# hover_controller_v2.net
KiCad netlist of a schematic drawn in EAGLE
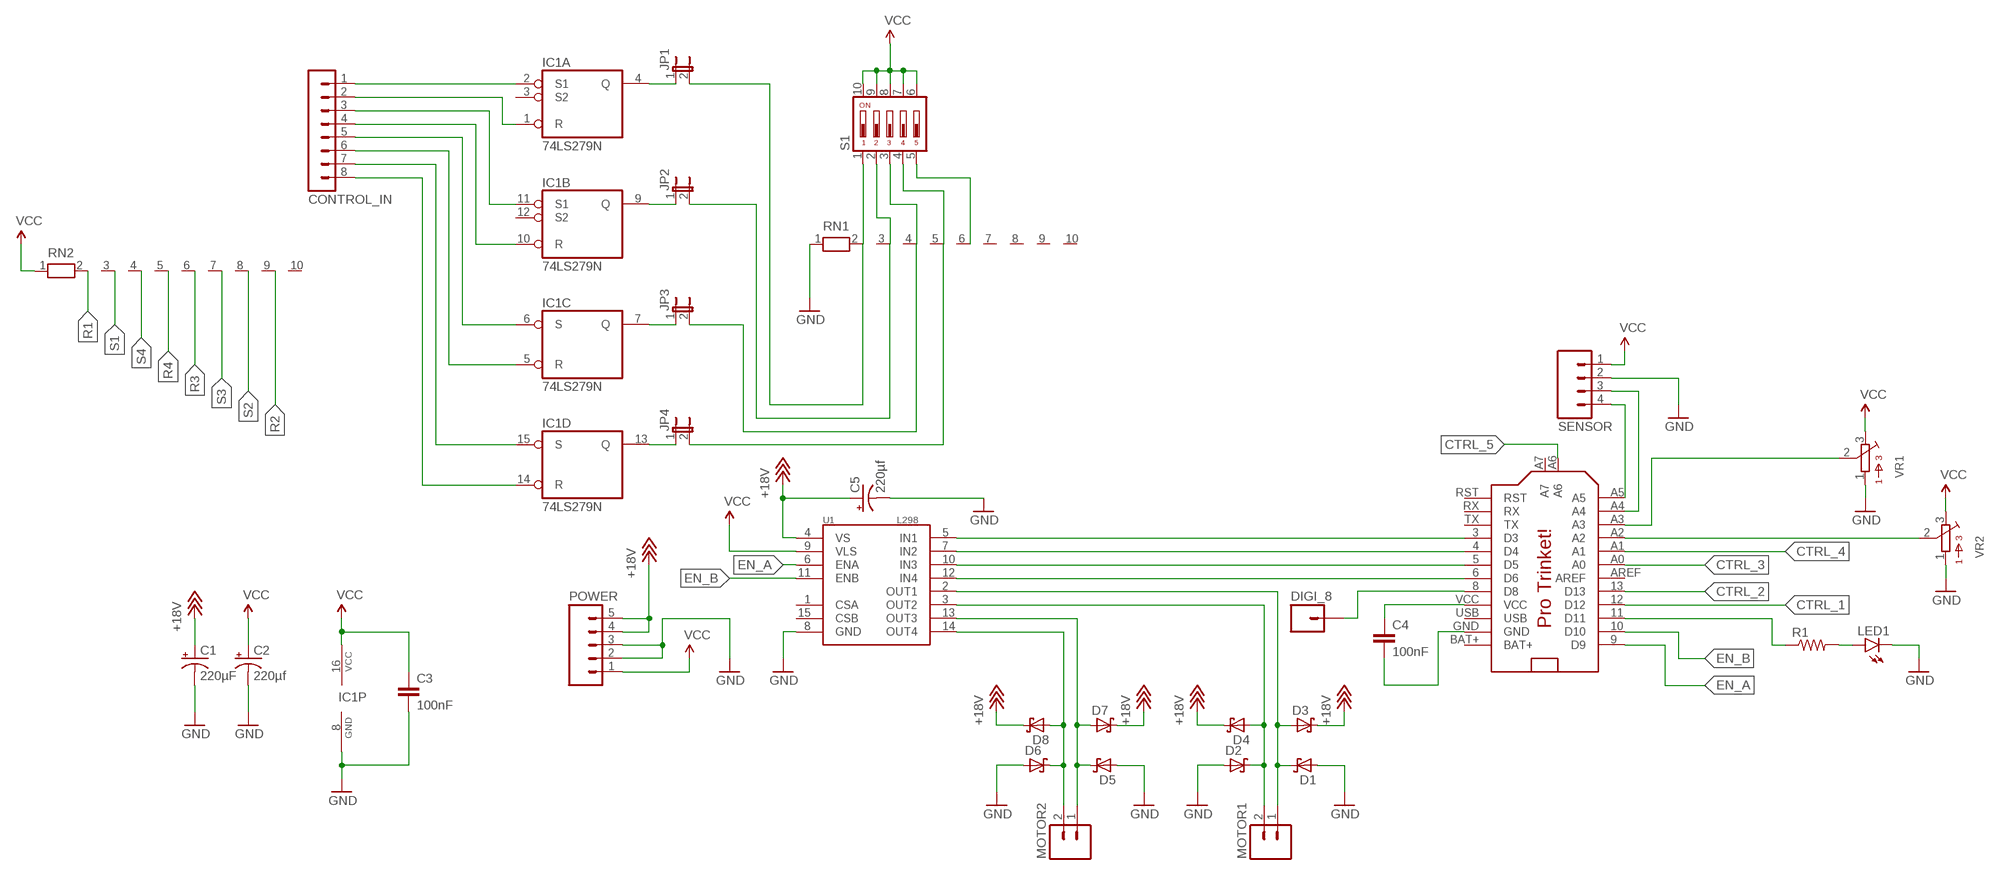
[diagram p0: schematic, sheet 1]

(export (version "E")
  (design (tool "Eeschema 10.0.6"))
  (components
    (comp (ref "C1")
      (value "220µF")
      (footprint "eagle-import:CPOL-RADIAL-10UF-25V")
      (libsource (lib "eagle-import") (part "CAP_POLPTH2"))
    )
    (comp (ref "C2")
      (value "220µf")
      (footprint "eagle-import:CPOL-RADIAL-10UF-25V")
      (libsource (lib "eagle-import") (part "CAP_POLPTH2"))
    )
    (comp (ref "C3")
      (value "100nF")
      (footprint "eagle-import:CAP-PTH-5MM")
      (libsource (lib "eagle-import") (part "CAPPTH1"))
    )
    (comp (ref "C4")
      (value "100nF")
      (footprint "eagle-import:CAP-PTH-5MM")
      (libsource (lib "eagle-import") (part "CAPPTH1"))
    )
    (comp (ref "C5")
      (value "220µf")
      (footprint "eagle-import:CPOL-RADIAL-10UF-25V")
      (libsource (lib "eagle-import") (part "CAP_POLPTH2"))
    )
    (comp (ref "CONTROL_IN")
      (value "MA08-1")
      (footprint "eagle-import:MA08-1")
      (libsource (lib "eagle-import") (part "MA08-1"))
    )
    (comp (ref "D1")
      (value "SCHOTTKY-DIODEDO35-7")
      (footprint "eagle-import:DO35-7")
      (libsource (lib "eagle-import") (part "SCHOTTKY-DIODEDO35-7"))
    )
    (comp (ref "D2")
      (value "SCHOTTKY-DIODEDO35-7")
      (footprint "eagle-import:DO35-7")
      (libsource (lib "eagle-import") (part "SCHOTTKY-DIODEDO35-7"))
    )
    (comp (ref "D3")
      (value "SCHOTTKY-DIODEDO35-7")
      (footprint "eagle-import:DO35-7")
      (libsource (lib "eagle-import") (part "SCHOTTKY-DIODEDO35-7"))
    )
    (comp (ref "D4")
      (value "SCHOTTKY-DIODEDO35-7")
      (footprint "eagle-import:DO35-7")
      (libsource (lib "eagle-import") (part "SCHOTTKY-DIODEDO35-7"))
    )
    (comp (ref "D5")
      (value "SCHOTTKY-DIODEDO35-7")
      (footprint "eagle-import:DO35-7")
      (libsource (lib "eagle-import") (part "SCHOTTKY-DIODEDO35-7"))
    )
    (comp (ref "D6")
      (value "SCHOTTKY-DIODEDO35-7")
      (footprint "eagle-import:DO35-7")
      (libsource (lib "eagle-import") (part "SCHOTTKY-DIODEDO35-7"))
    )
    (comp (ref "D7")
      (value "SCHOTTKY-DIODEDO35-7")
      (footprint "eagle-import:DO35-7")
      (libsource (lib "eagle-import") (part "SCHOTTKY-DIODEDO35-7"))
    )
    (comp (ref "D8")
      (value "SCHOTTKY-DIODEDO35-7")
      (footprint "eagle-import:DO35-7")
      (libsource (lib "eagle-import") (part "SCHOTTKY-DIODEDO35-7"))
    )
    (comp (ref "DIGI_8")
      (value "M01PTH")
      (footprint "eagle-import:1X01")
      (libsource (lib "eagle-import") (part "M01PTH"))
    )
    (comp (ref "IC1")
      (value "74LS279N")
      (footprint "eagle-import:DIL16")
      (libsource (lib "eagle-import") (part "74279NLS"))
    )
    (comp (ref "JP1")
      (value "JUMPER-2PTH")
      (footprint "eagle-import:1X02")
      (libsource (lib "eagle-import") (part "JUMPER-2PTH"))
    )
    (comp (ref "JP2")
      (value "JUMPER-2PTH")
      (footprint "eagle-import:1X02")
      (libsource (lib "eagle-import") (part "JUMPER-2PTH"))
    )
    (comp (ref "JP3")
      (value "JUMPER-2PTH")
      (footprint "eagle-import:1X02")
      (libsource (lib "eagle-import") (part "JUMPER-2PTH"))
    )
    (comp (ref "JP4")
      (value "JUMPER-2PTH")
      (footprint "eagle-import:1X02")
      (libsource (lib "eagle-import") (part "JUMPER-2PTH"))
    )
    (comp (ref "LED1")
      (value "LED-3MM-NO_SILK")
      (footprint "eagle-import:LED3MM-NS")
      (libsource (lib "eagle-import") (part "LED-3MM-NO_SILK"))
    )
    (comp (ref "MOTOR1")
      (value "M02PTH")
      (footprint "eagle-import:1X02")
      (libsource (lib "eagle-import") (part "M02PTH"))
    )
    (comp (ref "MOTOR2")
      (value "M02PTH")
      (footprint "eagle-import:1X02")
      (libsource (lib "eagle-import") (part "M02PTH"))
    )
    (comp (ref "POWER")
      (value "M05JST-VERT")
      (footprint "eagle-import:JST-5-PTH-VERT")
      (libsource (lib "eagle-import") (part "M05JST-VERT"))
    )
    (comp (ref "R1")
      (value "RESISTORPTH-1/4W")
      (footprint "eagle-import:AXIAL-0.4")
      (libsource (lib "eagle-import") (part "RESISTORPTH-1/4W"))
    )
    (comp (ref "RN1")
      (value "RN09")
      (footprint "eagle-import:RN-10")
      (libsource (lib "eagle-import") (part "RN09"))
    )
    (comp (ref "RN2")
      (value "RN09")
      (footprint "eagle-import:RN-10")
      (libsource (lib "eagle-import") (part "RN09"))
    )
    (comp (ref "S1")
      (value "DIP05YL")
      (footprint "eagle-import:DIP05YL")
      (libsource (lib "eagle-import") (part "DIP05YL"))
    )
    (comp (ref "SENSOR")
      (value "M04PTH")
      (footprint "eagle-import:1X04")
      (libsource (lib "eagle-import") (part "M04PTH"))
    )
    (comp (ref "U$1")
      (value "PRO_TRINKET")
      (footprint "eagle-import:PROTRINKET")
      (libsource (lib "eagle-import") (part "PRO_TRINKET"))
    )
    (comp (ref "U1")
      (value "L298")
      (footprint "eagle-import:MULTIWATT15")
      (libsource (lib "eagle-import") (part "L298"))
    )
    (comp (ref "VR1")
      (value "BOURNS_3362P_TRIMMERP")
      (footprint "eagle-import:BOURNS_3362P_TRIMMER")
      (libsource (lib "eagle-import") (part "BOURNS_3362P_TRIMMERP"))
    )
    (comp (ref "VR2")
      (value "BOURNS_3362P_TRIMMERP")
      (footprint "eagle-import:BOURNS_3362P_TRIMMER")
      (libsource (lib "eagle-import") (part "BOURNS_3362P_TRIMMERP"))
    )
  )
  (nets
    (net (code "1") (name "+18V") (class "Default")
      (node (ref "C1") (pin "1") (pinfunction "+_1") (pintype "passive"))
      (node (ref "C5") (pin "1") (pinfunction "+_1") (pintype "passive"))
      (node (ref "D3") (pin "C") (pinfunction "C_C") (pintype "passive"))
      (node (ref "D4") (pin "C") (pinfunction "C_C") (pintype "passive"))
      (node (ref "D7") (pin "C") (pinfunction "C_C") (pintype "passive"))
      (node (ref "D8") (pin "C") (pinfunction "C_C") (pintype "passive"))
      (node (ref "POWER") (pin "4") (pinfunction "4_4") (pintype "passive"))
      (node (ref "POWER") (pin "5") (pinfunction "5_5") (pintype "passive"))
      (node (ref "U1") (pin "4") (pinfunction "VS_4") (pintype "bidirectional"))
    )
    (net (code "2") (name "/BAT+") (class "Default")
      (node (ref "U$1") (pin "BAT+") (pinfunction "BAT+_BAT+") (pintype "power_in"))
    )
    (net (code "3") (name "/USB") (class "Default")
      (node (ref "U$1") (pin "USB") (pinfunction "USB_USB") (pintype "power_in"))
    )
    (net (code "4") (name "CTRL_1") (class "Default")
      (node (ref "JP1") (pin "2") (pinfunction "2_2") (pintype "passive"))
      (node (ref "RN1") (pin "2") (pinfunction "2_2") (pintype "passive"))
      (node (ref "S1") (pin "1") (pinfunction "1_1") (pintype "passive"))
      (node (ref "U$1") (pin "12") (pinfunction "D12_12") (pintype "bidirectional"))
    )
    (net (code "5") (name "CTRL_2") (class "Default")
      (node (ref "JP2") (pin "2") (pinfunction "2_2") (pintype "passive"))
      (node (ref "RN1") (pin "3") (pinfunction "3_3") (pintype "passive"))
      (node (ref "S1") (pin "2") (pinfunction "2_2") (pintype "passive"))
      (node (ref "U$1") (pin "13") (pinfunction "D13_13") (pintype "bidirectional"))
    )
    (net (code "6") (name "CTRL_3") (class "Default")
      (node (ref "JP3") (pin "2") (pinfunction "2_2") (pintype "passive"))
      (node (ref "RN1") (pin "4") (pinfunction "4_4") (pintype "passive"))
      (node (ref "S1") (pin "3") (pinfunction "3_3") (pintype "passive"))
      (node (ref "U$1") (pin "A0") (pinfunction "A0_A0") (pintype "bidirectional"))
    )
    (net (code "7") (name "CTRL_4") (class "Default")
      (node (ref "JP4") (pin "2") (pinfunction "2_2") (pintype "passive"))
      (node (ref "RN1") (pin "5") (pinfunction "5_5") (pintype "passive"))
      (node (ref "S1") (pin "4") (pinfunction "4_4") (pintype "passive"))
      (node (ref "U$1") (pin "A1") (pinfunction "A1_A1") (pintype "bidirectional"))
    )
    (net (code "8") (name "CTRL_5") (class "Default")
      (node (ref "RN1") (pin "6") (pinfunction "6_6") (pintype "passive"))
      (node (ref "S1") (pin "5") (pinfunction "5_5") (pintype "passive"))
      (node (ref "U$1") (pin "A6") (pinfunction "A6_A6") (pintype "passive"))
    )
    (net (code "9") (name "EN_A") (class "Default")
      (node (ref "U$1") (pin "9") (pinfunction "D9_9") (pintype "bidirectional"))
      (node (ref "U1") (pin "6") (pinfunction "ENA_6") (pintype "bidirectional"))
    )
    (net (code "10") (name "EN_B") (class "Default")
      (node (ref "U$1") (pin "10") (pinfunction "D10_10") (pintype "bidirectional"))
      (node (ref "U1") (pin "11") (pinfunction "ENB_11") (pintype "bidirectional"))
    )
    (net (code "11") (name "GND") (class "Default")
      (node (ref "C1") (pin "2") (pinfunction "-_2") (pintype "passive"))
      (node (ref "C2") (pin "2") (pinfunction "-_2") (pintype "passive"))
      (node (ref "C3") (pin "2") (pinfunction "2_2") (pintype "passive"))
      (node (ref "C5") (pin "2") (pinfunction "-_2") (pintype "passive"))
      (node (ref "D1") (pin "A") (pinfunction "A_A") (pintype "passive"))
      (node (ref "D2") (pin "A") (pinfunction "A_A") (pintype "passive"))
      (node (ref "D5") (pin "A") (pinfunction "A_A") (pintype "passive"))
      (node (ref "D6") (pin "A") (pinfunction "A_A") (pintype "passive"))
      (node (ref "IC1") (pin "8") (pinfunction "GND_8") (pintype "power_in"))
      (node (ref "LED1") (pin "K") (pinfunction "C_K") (pintype "passive"))
      (node (ref "POWER") (pin "2") (pinfunction "2_2") (pintype "passive"))
      (node (ref "POWER") (pin "3") (pinfunction "3_3") (pintype "passive"))
      (node (ref "RN1") (pin "1") (pinfunction "1_1") (pintype "passive"))
      (node (ref "SENSOR") (pin "2") (pinfunction "2_2") (pintype "passive"))
      (node (ref "U1") (pin "8") (pinfunction "GND_8") (pintype "bidirectional"))
      (node (ref "VR1") (pin "1") (pinfunction "1_1") (pintype "passive"))
      (node (ref "VR2") (pin "1") (pinfunction "1_1") (pintype "passive"))
    )
    (net (code "12") (name "Net-(C4-Pad1)") (class "Default")
      (node (ref "C4") (pin "1") (pinfunction "1_1") (pintype "passive"))
      (node (ref "U$1") (pin "VCC") (pinfunction "VCC_VCC") (pintype "power_in"))
    )
    (net (code "13") (name "Net-(C4-Pad2)") (class "Default")
      (node (ref "C4") (pin "2") (pinfunction "2_2") (pintype "passive"))
      (node (ref "U$1") (pin "GND") (pinfunction "GND_GND") (pintype "power_in"))
    )
    (net (code "14") (name "Net-(IC1A-Q)") (class "Default")
      (node (ref "IC1") (pin "4") (pinfunction "Q_4") (pintype "output"))
      (node (ref "JP1") (pin "1") (pinfunction "1_1") (pintype "passive"))
    )
    (net (code "15") (name "Net-(IC1B-Q)") (class "Default")
      (node (ref "IC1") (pin "9") (pinfunction "Q_9") (pintype "output"))
      (node (ref "JP2") (pin "1") (pinfunction "1_1") (pintype "passive"))
    )
    (net (code "16") (name "Net-(IC1C-Q)") (class "Default")
      (node (ref "IC1") (pin "7") (pinfunction "Q_7") (pintype "output"))
      (node (ref "JP3") (pin "1") (pinfunction "1_1") (pintype "passive"))
    )
    (net (code "17") (name "Net-(IC1D-Q)") (class "Default")
      (node (ref "IC1") (pin "13") (pinfunction "Q_13") (pintype "output"))
      (node (ref "JP4") (pin "1") (pinfunction "1_1") (pintype "passive"))
    )
    (net (code "18") (name "Net-(R1-1)") (class "Default")
      (node (ref "R1") (pin "P$1") (pinfunction "1_P$1") (pintype "passive"))
      (node (ref "U$1") (pin "11") (pinfunction "D11_11") (pintype "bidirectional"))
    )
    (net (code "19") (name "Net-(R1-2)") (class "Default")
      (node (ref "LED1") (pin "A") (pinfunction "A_A") (pintype "passive"))
      (node (ref "R1") (pin "P$2") (pinfunction "2_P$2") (pintype "passive"))
    )
    (net (code "20") (name "Net-(SENSOR-Pad3)") (class "Default")
      (node (ref "SENSOR") (pin "3") (pinfunction "3_3") (pintype "passive"))
      (node (ref "U$1") (pin "A4") (pinfunction "A4_A4") (pintype "bidirectional"))
    )
    (net (code "21") (name "Net-(SENSOR-Pad4)") (class "Default")
      (node (ref "SENSOR") (pin "4") (pinfunction "4_4") (pintype "passive"))
      (node (ref "U$1") (pin "A5") (pinfunction "A5_A5") (pintype "bidirectional"))
    )
    (net (code "22") (name "Net-(U$1-D3)") (class "Default")
      (node (ref "U$1") (pin "3") (pinfunction "D3_3") (pintype "bidirectional"))
      (node (ref "U1") (pin "5") (pinfunction "IN1_5") (pintype "bidirectional"))
    )
    (net (code "23") (name "Net-(U$1-D4)") (class "Default")
      (node (ref "U$1") (pin "4") (pinfunction "D4_4") (pintype "bidirectional"))
      (node (ref "U1") (pin "7") (pinfunction "IN2_7") (pintype "bidirectional"))
    )
    (net (code "24") (name "Net-(U$1-D5)") (class "Default")
      (node (ref "U$1") (pin "5") (pinfunction "D5_5") (pintype "bidirectional"))
      (node (ref "U1") (pin "10") (pinfunction "IN3_10") (pintype "bidirectional"))
    )
    (net (code "25") (name "Net-(U$1-D6)") (class "Default")
      (node (ref "U$1") (pin "6") (pinfunction "D6_6") (pintype "bidirectional"))
      (node (ref "U1") (pin "12") (pinfunction "IN4_12") (pintype "bidirectional"))
    )
    (net (code "26") (name "Net-(U$1-D8)") (class "Default")
      (node (ref "DIGI_8") (pin "1") (pinfunction "1_1") (pintype "passive"))
      (node (ref "U$1") (pin "8") (pinfunction "D8_8") (pintype "bidirectional"))
    )
    (net (code "27") (name "Net-(U$1-PadA2)") (class "Default")
      (node (ref "U$1") (pin "A2") (pinfunction "A2_A2") (pintype "bidirectional"))
      (node (ref "VR2") (pin "2") (pinfunction "2_2") (pintype "passive"))
    )
    (net (code "28") (name "Net-(U$1-PadA3)") (class "Default")
      (node (ref "U$1") (pin "A3") (pinfunction "A3_A3") (pintype "bidirectional"))
      (node (ref "VR1") (pin "2") (pinfunction "2_2") (pintype "passive"))
    )
    (net (code "29") (name "Net-(U1-OUT1)") (class "Default")
      (node (ref "D1") (pin "C") (pinfunction "C_C") (pintype "passive"))
      (node (ref "D3") (pin "A") (pinfunction "A_A") (pintype "passive"))
      (node (ref "MOTOR1") (pin "1") (pinfunction "1_1") (pintype "passive"))
      (node (ref "U1") (pin "2") (pinfunction "OUT1_2") (pintype "bidirectional"))
    )
    (net (code "30") (name "Net-(U1-OUT2)") (class "Default")
      (node (ref "D2") (pin "C") (pinfunction "C_C") (pintype "passive"))
      (node (ref "D4") (pin "A") (pinfunction "A_A") (pintype "passive"))
      (node (ref "MOTOR1") (pin "2") (pinfunction "2_2") (pintype "passive"))
      (node (ref "U1") (pin "3") (pinfunction "OUT2_3") (pintype "bidirectional"))
    )
    (net (code "31") (name "Net-(U1-OUT3)") (class "Default")
      (node (ref "D5") (pin "C") (pinfunction "C_C") (pintype "passive"))
      (node (ref "D7") (pin "A") (pinfunction "A_A") (pintype "passive"))
      (node (ref "MOTOR2") (pin "1") (pinfunction "1_1") (pintype "passive"))
      (node (ref "U1") (pin "13") (pinfunction "OUT3_13") (pintype "bidirectional"))
    )
    (net (code "32") (name "Net-(U1-OUT4)") (class "Default")
      (node (ref "D6") (pin "C") (pinfunction "C_C") (pintype "passive"))
      (node (ref "D8") (pin "A") (pinfunction "A_A") (pintype "passive"))
      (node (ref "MOTOR2") (pin "2") (pinfunction "2_2") (pintype "passive"))
      (node (ref "U1") (pin "14") (pinfunction "OUT4_14") (pintype "bidirectional"))
    )
    (net (code "33") (name "R1") (class "Default")
      (node (ref "CONTROL_IN") (pin "2") (pinfunction "2_2") (pintype "passive"))
      (node (ref "IC1") (pin "1") (pinfunction "R_1") (pintype "input"))
      (node (ref "RN2") (pin "2") (pinfunction "2_2") (pintype "passive"))
    )
    (net (code "34") (name "R2") (class "Default")
      (node (ref "CONTROL_IN") (pin "4") (pinfunction "4_4") (pintype "passive"))
      (node (ref "IC1") (pin "10") (pinfunction "R_10") (pintype "input"))
      (node (ref "RN2") (pin "9") (pinfunction "9_9") (pintype "passive"))
    )
    (net (code "35") (name "R3") (class "Default")
      (node (ref "CONTROL_IN") (pin "6") (pinfunction "6_6") (pintype "passive"))
      (node (ref "IC1") (pin "5") (pinfunction "R_5") (pintype "input"))
      (node (ref "RN2") (pin "6") (pinfunction "6_6") (pintype "passive"))
    )
    (net (code "36") (name "R4") (class "Default")
      (node (ref "CONTROL_IN") (pin "8") (pinfunction "8_8") (pintype "passive"))
      (node (ref "IC1") (pin "14") (pinfunction "R_14") (pintype "input"))
      (node (ref "RN2") (pin "5") (pinfunction "5_5") (pintype "passive"))
    )
    (net (code "37") (name "S1") (class "Default")
      (node (ref "CONTROL_IN") (pin "1") (pinfunction "1_1") (pintype "passive"))
      (node (ref "IC1") (pin "2") (pinfunction "S1_2") (pintype "input"))
      (node (ref "RN2") (pin "3") (pinfunction "3_3") (pintype "passive"))
    )
    (net (code "38") (name "S2") (class "Default")
      (node (ref "CONTROL_IN") (pin "3") (pinfunction "3_3") (pintype "passive"))
      (node (ref "IC1") (pin "11") (pinfunction "S1_11") (pintype "input"))
      (node (ref "RN2") (pin "8") (pinfunction "8_8") (pintype "passive"))
    )
    (net (code "39") (name "S3") (class "Default")
      (node (ref "CONTROL_IN") (pin "5") (pinfunction "5_5") (pintype "passive"))
      (node (ref "IC1") (pin "6") (pinfunction "S_6") (pintype "input"))
      (node (ref "RN2") (pin "7") (pinfunction "7_7") (pintype "passive"))
    )
    (net (code "40") (name "S4") (class "Default")
      (node (ref "CONTROL_IN") (pin "7") (pinfunction "7_7") (pintype "passive"))
      (node (ref "IC1") (pin "15") (pinfunction "S_15") (pintype "input"))
      (node (ref "RN2") (pin "4") (pinfunction "4_4") (pintype "passive"))
    )
    (net (code "41") (name "VCC") (class "Default")
      (node (ref "C2") (pin "1") (pinfunction "+_1") (pintype "passive"))
      (node (ref "C3") (pin "1") (pinfunction "1_1") (pintype "passive"))
      (node (ref "IC1") (pin "16") (pinfunction "VCC_16") (pintype "power_in"))
      (node (ref "POWER") (pin "1") (pinfunction "1_1") (pintype "passive"))
      (node (ref "RN2") (pin "1") (pinfunction "1_1") (pintype "passive"))
      (node (ref "S1") (pin "10") (pinfunction "10_10") (pintype "passive"))
      (node (ref "S1") (pin "6") (pinfunction "6_6") (pintype "passive"))
      (node (ref "S1") (pin "7") (pinfunction "7_7") (pintype "passive"))
      (node (ref "S1") (pin "8") (pinfunction "8_8") (pintype "passive"))
      (node (ref "S1") (pin "9") (pinfunction "9_9") (pintype "passive"))
      (node (ref "SENSOR") (pin "1") (pinfunction "1_1") (pintype "passive"))
      (node (ref "U1") (pin "9") (pinfunction "VLS_9") (pintype "bidirectional"))
      (node (ref "VR1") (pin "3") (pinfunction "3_3") (pintype "passive"))
      (node (ref "VR2") (pin "3") (pinfunction "3_3") (pintype "passive"))
    )
    (net (code "42") (name "unconnected-(IC1A-S2-Pad3)") (class "Default")
      (node (ref "IC1") (pin "3") (pinfunction "S2_3") (pintype "input"))
    )
    (net (code "43") (name "unconnected-(IC1B-S2-Pad12)") (class "Default")
      (node (ref "IC1") (pin "12") (pinfunction "S2_12") (pintype "input"))
    )
    (net (code "44") (name "unconnected-(RN1-Pad7)") (class "Default")
      (node (ref "RN1") (pin "7") (pinfunction "7_7") (pintype "passive"))
    )
    (net (code "45") (name "unconnected-(RN1-Pad8)") (class "Default")
      (node (ref "RN1") (pin "8") (pinfunction "8_8") (pintype "passive"))
    )
    (net (code "46") (name "unconnected-(RN1-Pad9)") (class "Default")
      (node (ref "RN1") (pin "9") (pinfunction "9_9") (pintype "passive"))
    )
    (net (code "47") (name "unconnected-(RN1-Pad10)") (class "Default")
      (node (ref "RN1") (pin "10") (pinfunction "10_10") (pintype "passive"))
    )
    (net (code "48") (name "unconnected-(RN2-Pad10)") (class "Default")
      (node (ref "RN2") (pin "10") (pinfunction "10_10") (pintype "passive"))
    )
    (net (code "49") (name "unconnected-(U$1-PadA7)") (class "Default")
      (node (ref "U$1") (pin "A7") (pinfunction "A7_A7") (pintype "passive"))
    )
    (net (code "50") (name "unconnected-(U$1-PadAREF)") (class "Default")
      (node (ref "U$1") (pin "AREF") (pinfunction "AREF_AREF") (pintype "passive"))
    )
    (net (code "51") (name "unconnected-(U$1-PadRST)") (class "Default")
      (node (ref "U$1") (pin "RST") (pinfunction "RST_RST") (pintype "passive"))
    )
    (net (code "52") (name "unconnected-(U$1-PadRX)") (class "Default")
      (node (ref "U$1") (pin "RX") (pinfunction "RX_RX") (pintype "bidirectional"))
    )
    (net (code "53") (name "unconnected-(U$1-PadTX)") (class "Default")
      (node (ref "U$1") (pin "TX") (pinfunction "TX_TX") (pintype "bidirectional"))
    )
    (net (code "54") (name "unconnected-(U1-CSA-Pad1)") (class "Default")
      (node (ref "U1") (pin "1") (pinfunction "CSA_1") (pintype "bidirectional"))
    )
    (net (code "55") (name "unconnected-(U1-CSB-Pad15)") (class "Default")
      (node (ref "U1") (pin "15") (pinfunction "CSB_15") (pintype "bidirectional"))
    )
  )
)
